# FD_Capacitance_Sensor_v15.net
KiCad netlist of a schematic drawn in EAGLE
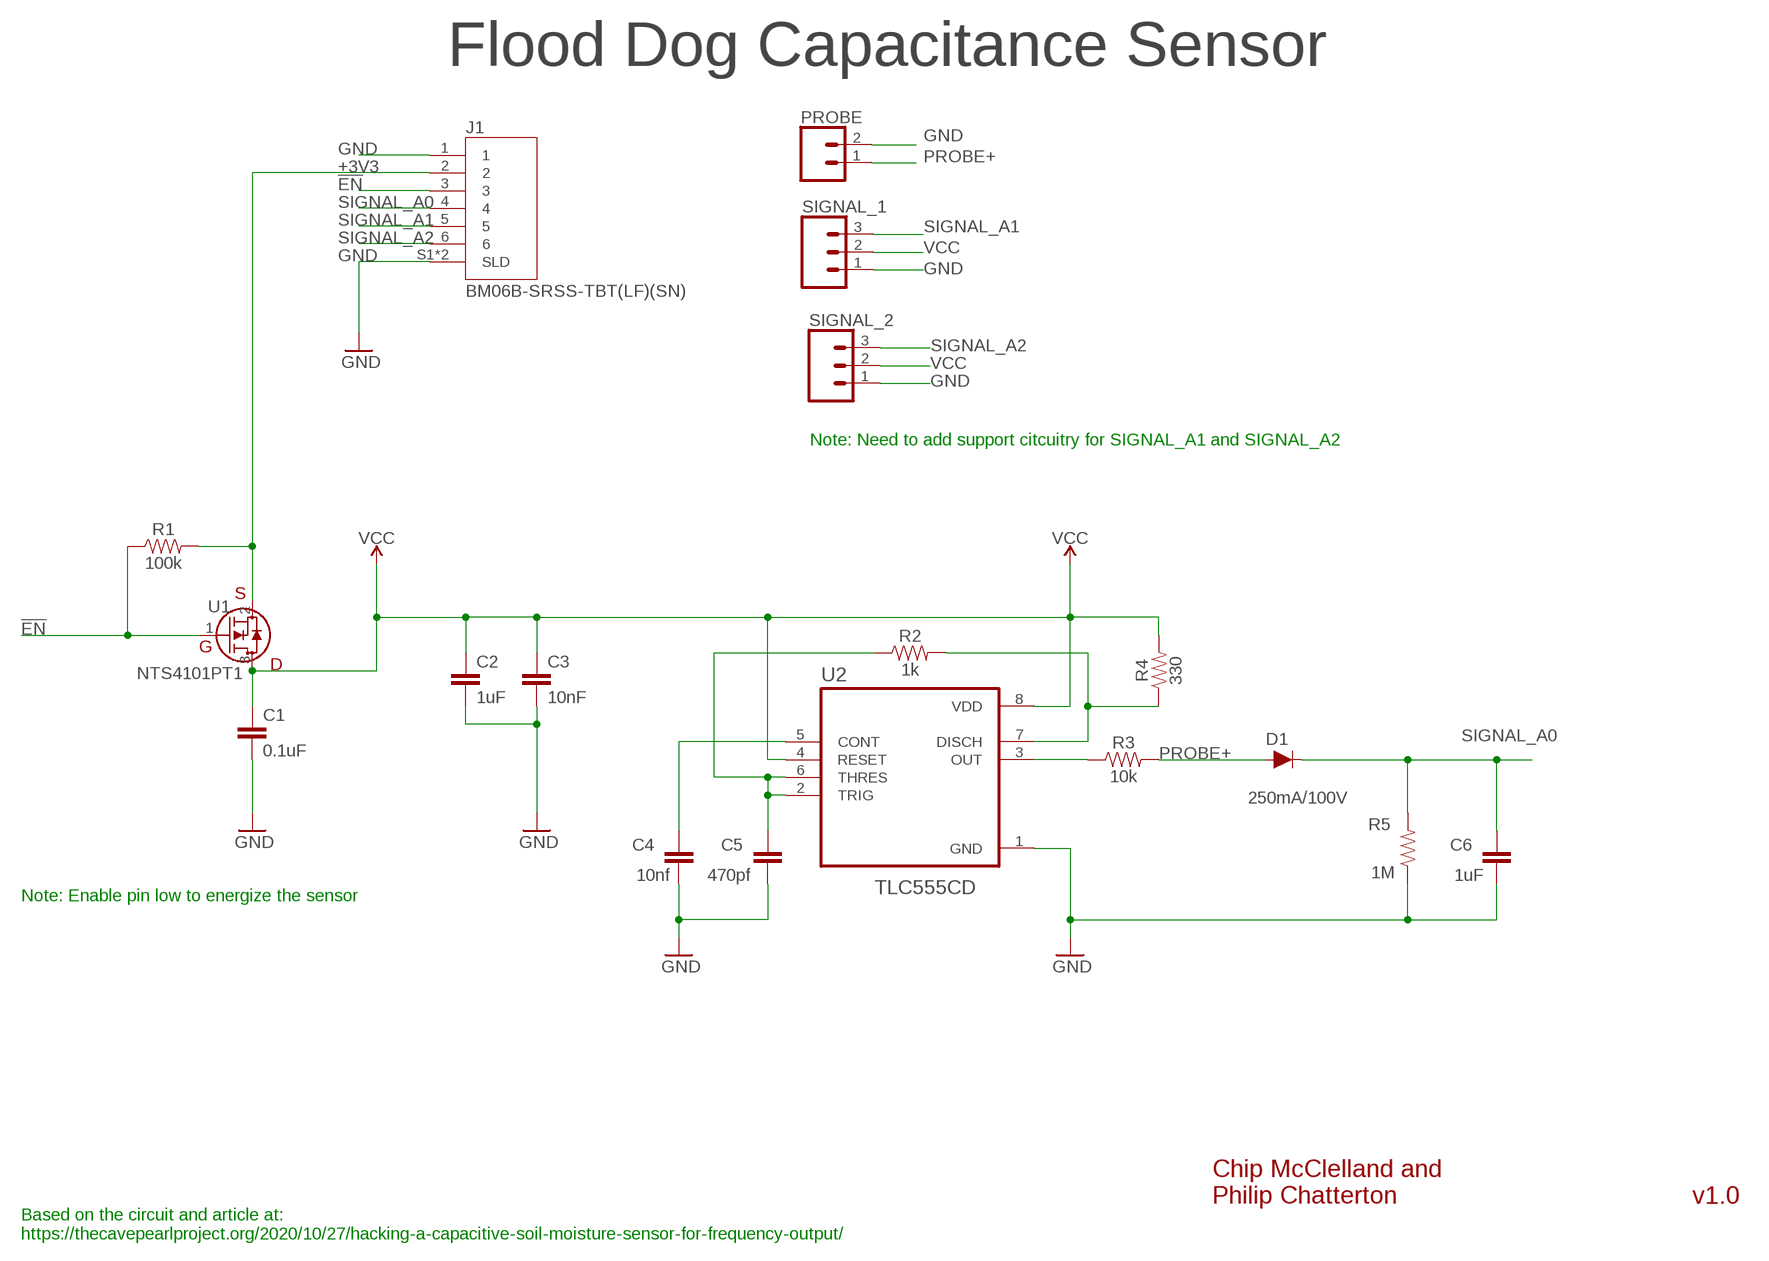
[diagram p0: schematic, sheet 1]

(export (version "E")
  (design (tool "Eeschema 10.0.6"))
  (components
    (comp (ref "C1")
      (value "0.1uF")
      (footprint "eagle-import:0805@1")
      (fields (field (name "HOUSEPART") "YES") (field (name "MPN") "MF-CAP-0805-0.1uF"))
      (libsource (lib "eagle-import") (part "CAP-MF-0.1UF-0805"))
    )
    (comp (ref "C2")
      (value "1uF")
      (footprint "eagle-import:0805@1")
      (fields (field (name "HOUSEPART") "yes") (field (name "MPN") "MF-CAP-0805-1uF"))
      (libsource (lib "eagle-import") (part "CAP-MF-1UF-0805"))
    )
    (comp (ref "C3")
      (value "10nF")
      (footprint "eagle-import:0805@1")
      (fields (field (name "HOUSEPART") "NO") (field (name "MPN") "C0805X103K1RAC3316"))
      (libsource (lib "eagle-import") (part "CAP-10NF-0805"))
    )
    (comp (ref "C4")
      (value "10nf")
      (footprint "eagle-import:C0805")
      (libsource (lib "eagle-import") (part "C-EUC0805"))
    )
    (comp (ref "C5")
      (value "470pf")
      (footprint "eagle-import:C0805")
      (libsource (lib "eagle-import") (part "C-EUC0805"))
    )
    (comp (ref "C6")
      (value "1uF")
      (footprint "eagle-import:C0805")
      (libsource (lib "eagle-import") (part "C-EUC0805"))
    )
    (comp (ref "D1")
      (value "250mA/100V")
      (footprint "eagle-import:SOD-323")
      (fields (field (name "MPN") "BAS16HT1G"))
      (libsource (lib "eagle-import") (part "DIODE-BAS16J"))
    )
    (comp (ref "J1")
      (value "BM06B-SRSS-TBT(LF)(SN)")
      (footprint "eagle-import:JST_BM06B-SRSS-TB(LF)(SN)")
      (libsource (lib "eagle-import") (part "BM06B-SRSS-TBT(LF)(SN)"))
    )
    (comp (ref "PROBE")
      (value "CONN_02")
      (footprint "eagle-import:1X02")
      (libsource (lib "eagle-import") (part "CONN_02"))
    )
    (comp (ref "R1")
      (value "100k")
      (footprint "eagle-import:0805")
      (fields (field (name "MPN") "MF-RES-0805-100K") (field (name "MPN_1") "MF-RES-0805-100K"))
      (libsource (lib "eagle-import") (part "RESISTOR-MF-100K-0805"))
    )
    (comp (ref "R2")
      (value "1k")
      (footprint "eagle-import:0805")
      (fields (field (name "HOUSEPART") "YES") (field (name "MPN") "MF-RES-0805-1K"))
      (libsource (lib "eagle-import") (part "RESISTOR-MF-1K-0805"))
    )
    (comp (ref "R3")
      (value "10k")
      (footprint "eagle-import:0805")
      (fields (field (name "MPN") "MF-RES-0805-10K"))
      (libsource (lib "eagle-import") (part "RESISTOR-MF-10K-0805"))
    )
    (comp (ref "R4")
      (value "330")
      (footprint "eagle-import:0805")
      (fields (field (name "HOUSEPART") "YES") (field (name "MPN") "MF-RES-0805-330"))
      (libsource (lib "eagle-import") (part "RESISTOR-MF-330-0805"))
    )
    (comp (ref "R5")
      (value "1M")
      (footprint "eagle-import:0805")
      (fields (field (name "HOUSEPART") "YES") (field (name "MPN") "MF-RES-0805-1K"))
      (libsource (lib "eagle-import") (part "RESISTOR-MF-1K-0805"))
    )
    (comp (ref "SIGNAL_1")
      (value "CONN_03")
      (footprint "eagle-import:1X03")
      (libsource (lib "eagle-import") (part "CONN_03"))
    )
    (comp (ref "SIGNAL_2")
      (value "CONN_03")
      (footprint "eagle-import:1X03")
      (libsource (lib "eagle-import") (part "CONN_03"))
    )
    (comp (ref "U1")
      (value "NTS4101PT1")
      (footprint "eagle-import:SOT_101PT1_ONS")
      (libsource (lib "eagle-import") (part "NTS4101PT1"))
    )
    (comp (ref "U2")
      (value "TLC555CD")
      (footprint "eagle-import:SOIC127P599X175-8N")
      (fields (field (name "DIGI-KEY_PART_NUMBER") "296-52992-ND") (field (name "MF") "Texas Instruments"))
      (libsource (lib "eagle-import") (part "TLC555CD"))
    )
  )
  (nets
    (net (code "1") (name "/+3V3") (class "Default")
      (node (ref "J1") (pin "2") (pinfunction "2_2") (pintype "passive"))
      (node (ref "R1") (pin "2") (pinfunction "2_2") (pintype "passive"))
      (node (ref "U1") (pin "2") (pinfunction "S_2") (pintype "passive"))
    )
    (net (code "2") (name "/PROBE+") (class "Default")
      (node (ref "D1") (pin "A") (pinfunction "A_A") (pintype "passive"))
      (node (ref "PROBE") (pin "1") (pinfunction "1_1") (pintype "passive"))
      (node (ref "R3") (pin "2") (pinfunction "2_2") (pintype "passive"))
    )
    (net (code "3") (name "/SIGNAL_A0") (class "Default")
      (node (ref "C6") (pin "2") (pinfunction "2_2") (pintype "passive"))
      (node (ref "D1") (pin "C") (pinfunction "C_C") (pintype "passive"))
      (node (ref "J1") (pin "4") (pinfunction "4_4") (pintype "passive"))
      (node (ref "R5") (pin "2") (pinfunction "2_2") (pintype "passive"))
    )
    (net (code "4") (name "/SIGNAL_A1") (class "Default")
      (node (ref "J1") (pin "5") (pinfunction "5_5") (pintype "passive"))
      (node (ref "SIGNAL_1") (pin "3") (pinfunction "3_3") (pintype "passive"))
    )
    (net (code "5") (name "/SIGNAL_A2") (class "Default")
      (node (ref "J1") (pin "6") (pinfunction "6_6") (pintype "passive"))
      (node (ref "SIGNAL_2") (pin "3") (pinfunction "3_3") (pintype "passive"))
    )
    (net (code "6") (name "/~{EN}") (class "Default")
      (node (ref "J1") (pin "3") (pinfunction "3_3") (pintype "passive"))
      (node (ref "R1") (pin "1") (pinfunction "1_1") (pintype "passive"))
      (node (ref "U1") (pin "1") (pinfunction "G_1") (pintype "passive"))
    )
    (net (code "7") (name "GND") (class "Default")
      (node (ref "C1") (pin "2") (pinfunction "2_2") (pintype "passive"))
      (node (ref "C2") (pin "2") (pinfunction "2_2") (pintype "passive"))
      (node (ref "C3") (pin "2") (pinfunction "2_2") (pintype "passive"))
      (node (ref "C4") (pin "1") (pinfunction "1_1") (pintype "passive"))
      (node (ref "C5") (pin "1") (pinfunction "1_1") (pintype "passive"))
      (node (ref "C6") (pin "1") (pinfunction "1_1") (pintype "passive"))
      (node (ref "J1") (pin "1") (pinfunction "1_1") (pintype "passive"))
      (node (ref "J1") (pin "S1") (pinfunction "SLD_S1") (pintype "passive"))
      (node (ref "J1") (pin "S2") (pinfunction "SLD_S2") (pintype "passive"))
      (node (ref "PROBE") (pin "2") (pinfunction "2_2") (pintype "passive"))
      (node (ref "R5") (pin "1") (pinfunction "1_1") (pintype "passive"))
      (node (ref "SIGNAL_1") (pin "1") (pinfunction "1_1") (pintype "passive"))
      (node (ref "SIGNAL_2") (pin "1") (pinfunction "1_1") (pintype "passive"))
      (node (ref "U2") (pin "1") (pinfunction "GND_1") (pintype "power_in"))
    )
    (net (code "8") (name "Net-(U2-CONT)") (class "Default")
      (node (ref "C4") (pin "2") (pinfunction "2_2") (pintype "passive"))
      (node (ref "U2") (pin "5") (pinfunction "CONT_5") (pintype "input"))
    )
    (net (code "9") (name "Net-(U2-DISCH)") (class "Default")
      (node (ref "R2") (pin "2") (pinfunction "2_2") (pintype "passive"))
      (node (ref "R4") (pin "1") (pinfunction "1_1") (pintype "passive"))
      (node (ref "U2") (pin "7") (pinfunction "DISCH_7") (pintype "output"))
    )
    (net (code "10") (name "Net-(U2-OUT)") (class "Default")
      (node (ref "R3") (pin "1") (pinfunction "1_1") (pintype "passive"))
      (node (ref "U2") (pin "3") (pinfunction "OUT_3") (pintype "output"))
    )
    (net (code "11") (name "Net-(U2-THRES)") (class "Default")
      (node (ref "C5") (pin "2") (pinfunction "2_2") (pintype "passive"))
      (node (ref "R2") (pin "1") (pinfunction "1_1") (pintype "passive"))
      (node (ref "U2") (pin "2") (pinfunction "TRIG_2") (pintype "input"))
      (node (ref "U2") (pin "6") (pinfunction "THRES_6") (pintype "input"))
    )
    (net (code "12") (name "VCC") (class "Default")
      (node (ref "C1") (pin "1") (pinfunction "1_1") (pintype "passive"))
      (node (ref "C2") (pin "1") (pinfunction "1_1") (pintype "passive"))
      (node (ref "C3") (pin "1") (pinfunction "1_1") (pintype "passive"))
      (node (ref "R4") (pin "2") (pinfunction "2_2") (pintype "passive"))
      (node (ref "SIGNAL_1") (pin "2") (pinfunction "2_2") (pintype "passive"))
      (node (ref "SIGNAL_2") (pin "2") (pinfunction "2_2") (pintype "passive"))
      (node (ref "U1") (pin "3") (pinfunction "D_3") (pintype "passive"))
      (node (ref "U2") (pin "4") (pinfunction "RESET_4") (pintype "input"))
      (node (ref "U2") (pin "8") (pinfunction "VDD_8") (pintype "power_in"))
    )
  )
)
